# SI7021-V1_0.net
KiCad netlist of a schematic drawn in EAGLE
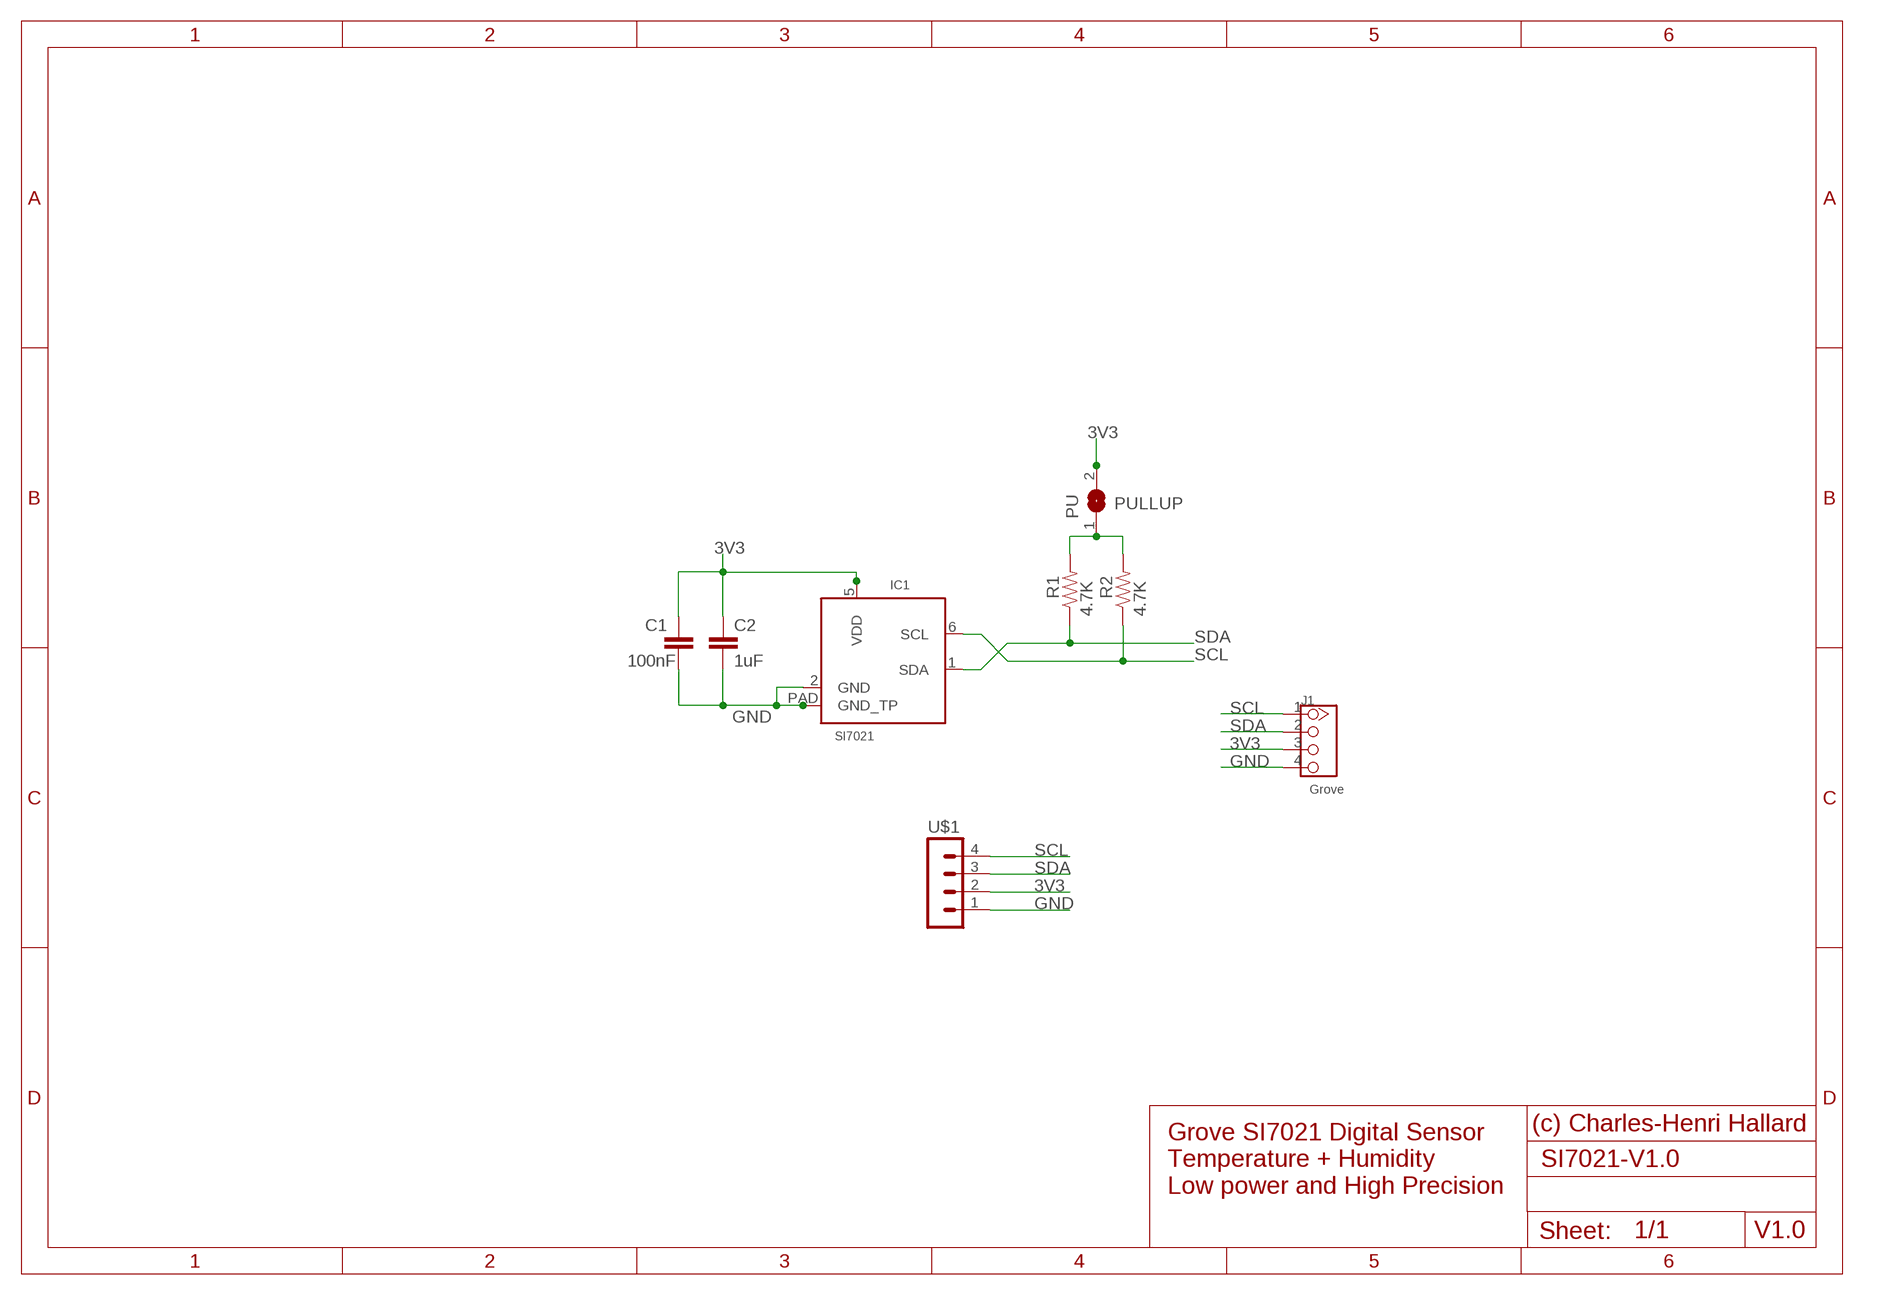
[diagram p0: schematic, sheet 1]

(export (version "E")
  (design (tool "Eeschema 10.0.6"))
  (components
    (comp (ref "C1")
      (value "100nF")
      (footprint "eagle-import:0805-CAP")
      (libsource (lib "eagle-import") (part "CAP0805-CAP"))
    )
    (comp (ref "C2")
      (value "1uF")
      (footprint "eagle-import:0805-CAP")
      (libsource (lib "eagle-import") (part "CAP0805-CAP"))
    )
    (comp (ref "IC1")
      (value "SI7021")
      (footprint "eagle-import:DFN6-3X3-LONG")
      (libsource (lib "eagle-import") (part "SI7020'LONG'"))
    )
    (comp (ref "J1")
      (value "Grove")
      (footprint "eagle-import:4P-2.0")
      (libsource (lib "eagle-import") (part "TWIG-4P-2.0-2.0"))
    )
    (comp (ref "PU")
      (value "SOLDERJUMPERREFLOW_NOPASTE")
      (footprint "eagle-import:SOLDERJUMPER_REFLOW_NOPASTE")
      (libsource (lib "eagle-import") (part "SOLDERJUMPERREFLOW_NOPASTE"))
    )
    (comp (ref "R1")
      (value "4.7K")
      (footprint "eagle-import:0805-RES")
      (libsource (lib "eagle-import") (part "RESISTOR0805-RES"))
    )
    (comp (ref "R2")
      (value "4.7K")
      (footprint "eagle-import:0805-RES")
      (libsource (lib "eagle-import") (part "RESISTOR0805-RES"))
    )
    (comp (ref "U$1")
      (value "CON_HEADER_1X04'SMALL''")
      (footprint "eagle-import:M1X4")
      (libsource (lib "eagle-import") (part "CON_HEADER_1X04'SMALL''"))
    )
  )
  (nets
    (net (code "1") (name "/3V3") (class "Default")
      (node (ref "C1") (pin "1") (pinfunction "1_1") (pintype "passive"))
      (node (ref "C2") (pin "1") (pinfunction "1_1") (pintype "passive"))
      (node (ref "IC1") (pin "5") (pinfunction "VDD_5") (pintype "bidirectional"))
      (node (ref "J1") (pin "3") (pinfunction "3_3") (pintype "bidirectional"))
      (node (ref "PU") (pin "2") (pinfunction "2_2") (pintype "passive"))
      (node (ref "U$1") (pin "2") (pinfunction "2_2") (pintype "passive"))
    )
    (net (code "2") (name "/GND") (class "Default")
      (node (ref "C1") (pin "2") (pinfunction "2_2") (pintype "passive"))
      (node (ref "C2") (pin "2") (pinfunction "2_2") (pintype "passive"))
      (node (ref "IC1") (pin "2") (pinfunction "GND_2") (pintype "bidirectional"))
      (node (ref "IC1") (pin "PAD") (pinfunction "GND_TP_PAD") (pintype "bidirectional"))
      (node (ref "J1") (pin "4") (pinfunction "4_4") (pintype "bidirectional"))
      (node (ref "U$1") (pin "1") (pinfunction "1_1") (pintype "passive"))
    )
    (net (code "3") (name "/PULLUP") (class "Default")
      (node (ref "PU") (pin "1") (pinfunction "1_1") (pintype "passive"))
      (node (ref "R1") (pin "2") (pinfunction "2_2") (pintype "passive"))
      (node (ref "R2") (pin "2") (pinfunction "2_2") (pintype "passive"))
    )
    (net (code "4") (name "/SCL") (class "Default")
      (node (ref "IC1") (pin "6") (pinfunction "SCL_6") (pintype "bidirectional"))
      (node (ref "J1") (pin "1") (pinfunction "1_1") (pintype "bidirectional"))
      (node (ref "R2") (pin "1") (pinfunction "1_1") (pintype "passive"))
      (node (ref "U$1") (pin "4") (pinfunction "4_4") (pintype "passive"))
    )
    (net (code "5") (name "/SDA") (class "Default")
      (node (ref "IC1") (pin "1") (pinfunction "SDA_1") (pintype "bidirectional"))
      (node (ref "J1") (pin "2") (pinfunction "2_2") (pintype "bidirectional"))
      (node (ref "R1") (pin "1") (pinfunction "1_1") (pintype "passive"))
      (node (ref "U$1") (pin "3") (pinfunction "3_3") (pintype "passive"))
    )
  )
)
